# Controller.net
KiCad netlist of a schematic drawn in EAGLE
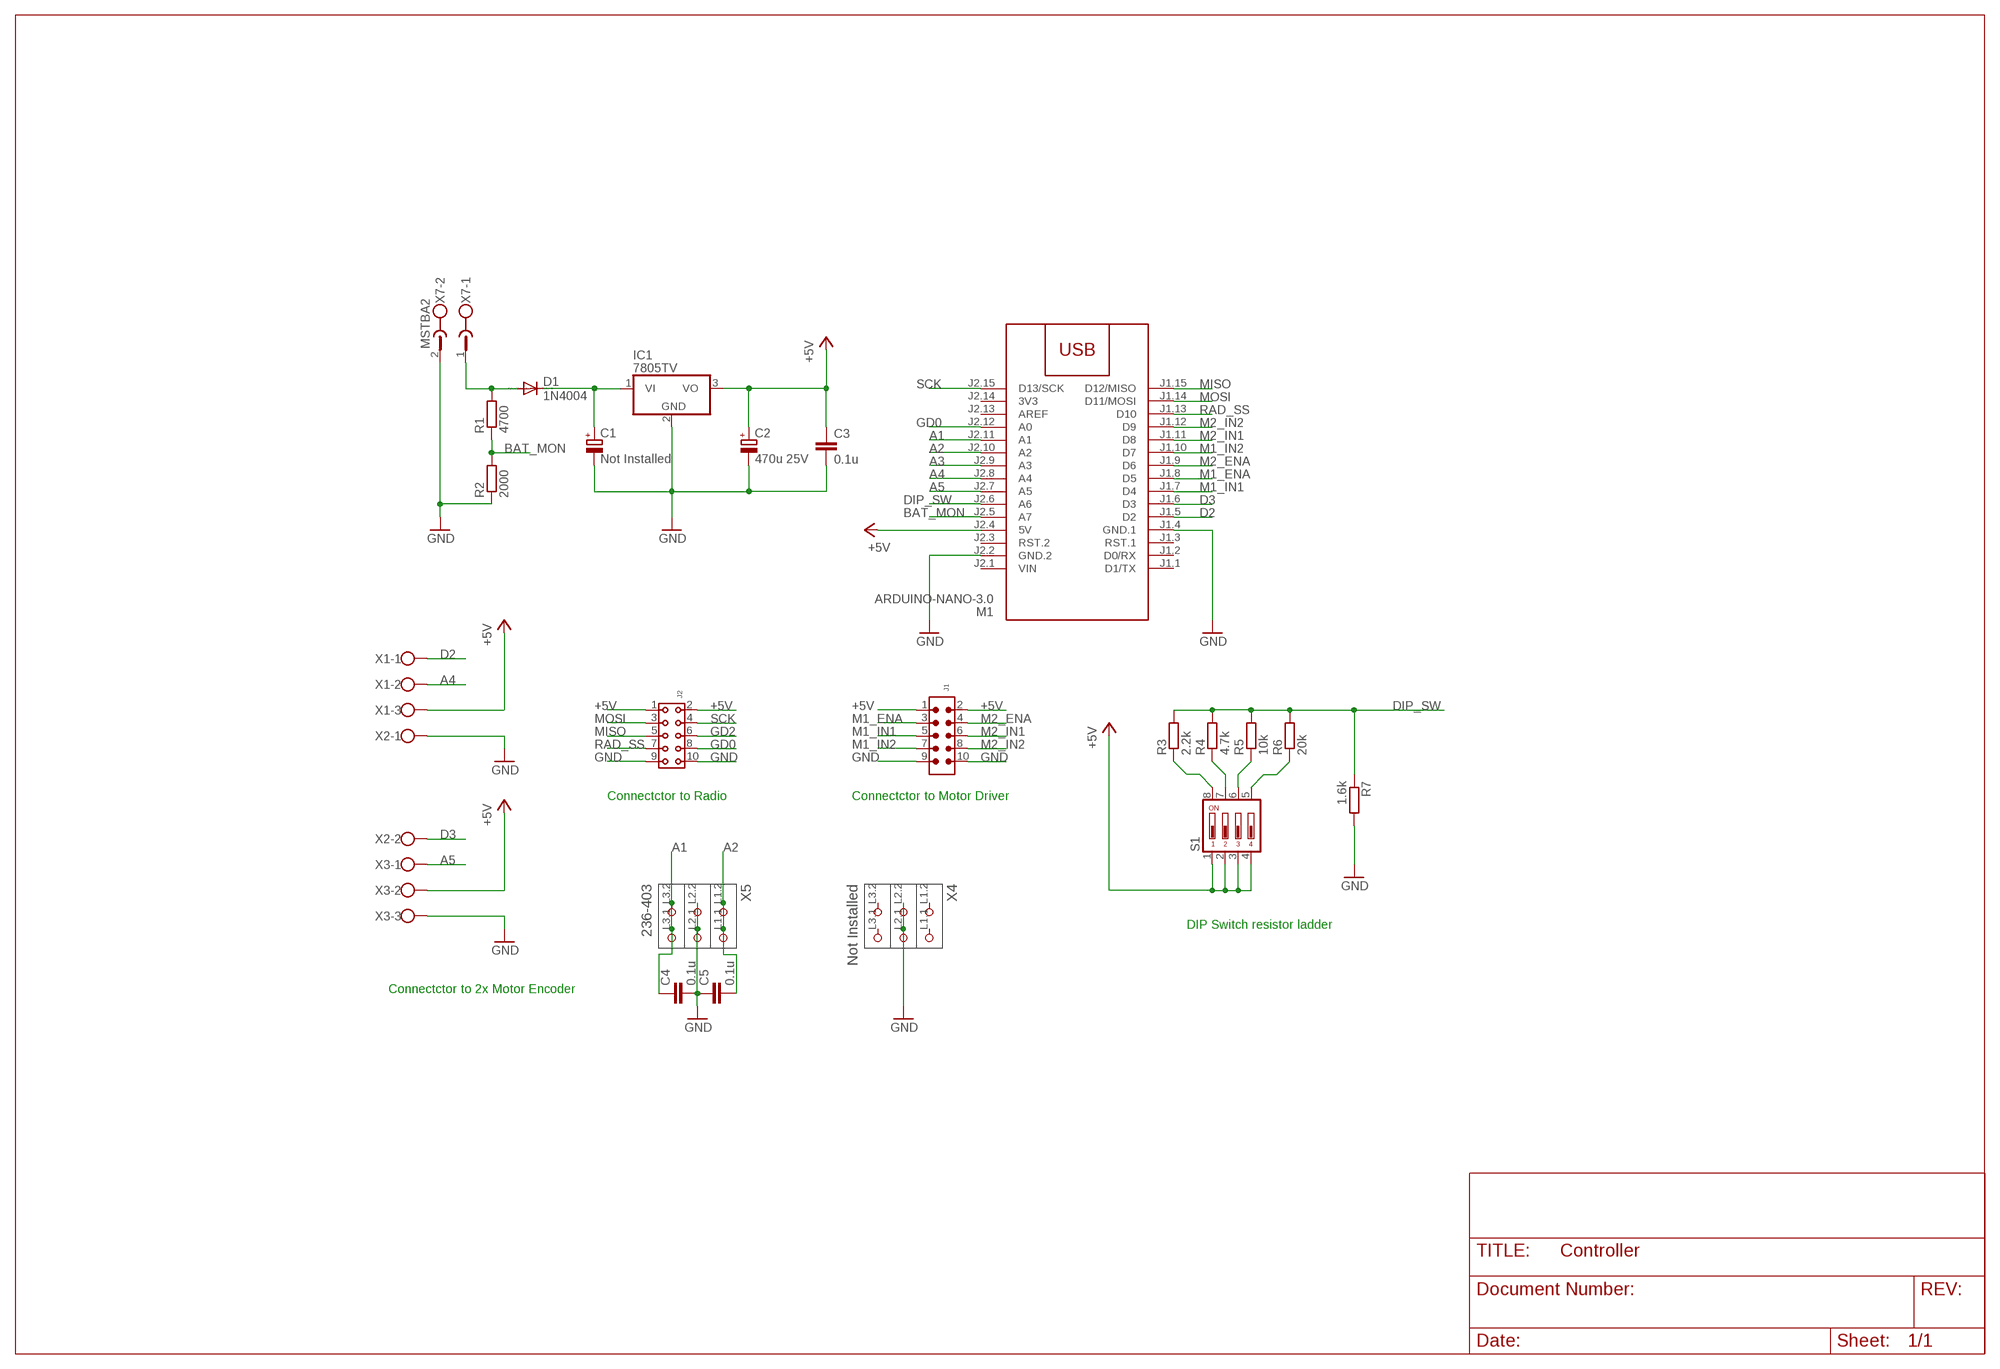
[diagram p0: schematic, sheet 1]

(export (version "E")
  (design (tool "Eeschema 10.0.6"))
  (components
    (comp (ref "C1")
      (value "Not Installed")
      (footprint "eagle-import:EB20D")
      (libsource (lib "eagle-import") (part "CPOL-EUE10-20"))
    )
    (comp (ref "C2")
      (value "470u 25V")
      (footprint "eagle-import:EB20D")
      (libsource (lib "eagle-import") (part "CPOL-EUE10-20"))
    )
    (comp (ref "C3")
      (value "0.1u")
      (footprint "eagle-import:C050-030X075")
      (libsource (lib "eagle-import") (part "C-EU050-030X075"))
    )
    (comp (ref "C4")
      (value "0.1u")
      (footprint "eagle-import:C050-030X075")
      (libsource (lib "eagle-import") (part "C-EU050-030X075"))
    )
    (comp (ref "C5")
      (value "0.1u")
      (footprint "eagle-import:C050-030X075")
      (libsource (lib "eagle-import") (part "C-EU050-030X075"))
    )
    (comp (ref "D1")
      (value "1N4004")
      (footprint "eagle-import:DO41-10")
      (libsource (lib "eagle-import") (part "1N4004"))
    )
    (comp (ref "IC1")
      (value "7805TV")
      (footprint "eagle-import:TO220V")
      (libsource (lib "eagle-import") (part "78TV05"))
    )
    (comp (ref "J1")
      (value "6120XX21621_61201021621")
      (footprint "eagle-import:61201021621")
      (libsource (lib "eagle-import") (part "6120XX21621_61201021621"))
    )
    (comp (ref "J2")
      (value "6130XX21821_61301021821")
      (footprint "eagle-import:61301021821")
      (libsource (lib "eagle-import") (part "6130XX21821_61301021821"))
    )
    (comp (ref "M1")
      (value "ARDUINO-NANO-3.0")
      (footprint "eagle-import:ARDUINO-NANO-3.0")
      (libsource (lib "eagle-import") (part "ARDUINO-NANO-3.0"))
    )
    (comp (ref "R1")
      (value "4700")
      (footprint "eagle-import:0207_12")
      (libsource (lib "eagle-import") (part "R-EU_0207/12"))
    )
    (comp (ref "R2")
      (value "2000")
      (footprint "eagle-import:0207_7")
      (libsource (lib "eagle-import") (part "R-EU_0207/7"))
    )
    (comp (ref "R3")
      (value "2.2k")
      (footprint "eagle-import:0207_5V")
      (libsource (lib "eagle-import") (part "R-EU_0207/5V"))
    )
    (comp (ref "R4")
      (value "4.7k")
      (footprint "eagle-import:0207_5V")
      (libsource (lib "eagle-import") (part "R-EU_0207/5V"))
    )
    (comp (ref "R5")
      (value "10k")
      (footprint "eagle-import:0207_5V")
      (libsource (lib "eagle-import") (part "R-EU_0207/5V"))
    )
    (comp (ref "R6")
      (value "20k")
      (footprint "eagle-import:0207_5V")
      (libsource (lib "eagle-import") (part "R-EU_0207/5V"))
    )
    (comp (ref "R7")
      (value "1.6k")
      (footprint "eagle-import:0207_5V")
      (libsource (lib "eagle-import") (part "R-EU_0207/5V"))
    )
    (comp (ref "S1")
      (value "DIP04YL")
      (footprint "eagle-import:DIP04YL")
      (libsource (lib "eagle-import") (part "DIP04YL"))
    )
    (comp (ref "X1")
      (value "W237-103")
      (footprint "eagle-import:W237-103")
      (fields (field (name "MPN") "237-103"))
      (libsource (lib "eagle-import") (part "W237-103"))
    )
    (comp (ref "X2")
      (value "W237-102")
      (footprint "eagle-import:W237-102")
      (fields (field (name "MPN") "237-102"))
      (libsource (lib "eagle-import") (part "W237-102"))
    )
    (comp (ref "X3")
      (value "W237-103")
      (footprint "eagle-import:W237-103")
      (fields (field (name "MPN") "237-103"))
      (libsource (lib "eagle-import") (part "W237-103"))
    )
    (comp (ref "X4")
      (value "Not Installed")
      (footprint "eagle-import:P-236-403")
      (libsource (lib "eagle-import") (part "236-403"))
    )
    (comp (ref "X5")
      (value "236-403")
      (footprint "eagle-import:P-236-403")
      (libsource (lib "eagle-import") (part "236-403"))
    )
    (comp (ref "X7")
      (value "MSTBA2")
      (footprint "eagle-import:MSTBA2")
      (fields (field (name "MF") "FARNELL") (field (name "MPN") "1757242"))
      (libsource (lib "eagle-import") (part "MSTBA2"))
    )
  )
  (nets
    (net (code "1") (name "+5V") (class "Default")
      (node (ref "C2") (pin "+") (pinfunction "+_+") (pintype "passive"))
      (node (ref "C3") (pin "1") (pinfunction "1_1") (pintype "passive"))
      (node (ref "IC1") (pin "3") (pinfunction "VO_3") (pintype "passive"))
      (node (ref "J1") (pin "1") (pinfunction "1_1") (pintype "passive"))
      (node (ref "J1") (pin "2") (pinfunction "2_2") (pintype "passive"))
      (node (ref "J2") (pin "1") (pinfunction "1_1") (pintype "passive"))
      (node (ref "J2") (pin "2") (pinfunction "2_2") (pintype "passive"))
      (node (ref "M1") (pin "J2.4") (pinfunction "5V_J2.4") (pintype "power_in"))
      (node (ref "S1") (pin "1") (pinfunction "1_1") (pintype "passive"))
      (node (ref "S1") (pin "2") (pinfunction "2_2") (pintype "passive"))
      (node (ref "S1") (pin "3") (pinfunction "3_3") (pintype "passive"))
      (node (ref "S1") (pin "4") (pinfunction "4_4") (pintype "passive"))
      (node (ref "X1") (pin "3") (pinfunction "KL_3") (pintype "passive"))
      (node (ref "X3") (pin "2") (pinfunction "KL_2") (pintype "passive"))
    )
    (net (code "2") (name "/3V3") (class "Default")
      (node (ref "M1") (pin "J2.14") (pinfunction "3V3_J2.14") (pintype "power_in"))
    )
    (net (code "3") (name "/A1") (class "Default")
      (node (ref "C4") (pin "1") (pinfunction "1_1") (pintype "passive"))
      (node (ref "M1") (pin "J2.11") (pinfunction "A1_J2.11") (pintype "bidirectional"))
      (node (ref "X5") (pin "L3.1") (pinfunction "P3.1_L3.1") (pintype "bidirectional"))
      (node (ref "X5") (pin "L3.2") (pinfunction "P3.2_L3.2") (pintype "bidirectional"))
    )
    (net (code "4") (name "/A2") (class "Default")
      (node (ref "C5") (pin "2") (pinfunction "2_2") (pintype "passive"))
      (node (ref "M1") (pin "J2.10") (pinfunction "A2_J2.10") (pintype "bidirectional"))
      (node (ref "X5") (pin "L1.1") (pinfunction "P1.1_L1.1") (pintype "bidirectional"))
      (node (ref "X5") (pin "L1.2") (pinfunction "P1.2_L1.2") (pintype "bidirectional"))
    )
    (net (code "5") (name "/A3") (class "Default")
      (node (ref "M1") (pin "J2.9") (pinfunction "A3_J2.9") (pintype "bidirectional"))
    )
    (net (code "6") (name "/A4") (class "Default")
      (node (ref "M1") (pin "J2.8") (pinfunction "A4_J2.8") (pintype "bidirectional"))
      (node (ref "X1") (pin "2") (pinfunction "KL_2") (pintype "passive"))
    )
    (net (code "7") (name "/A5") (class "Default")
      (node (ref "M1") (pin "J2.7") (pinfunction "A5_J2.7") (pintype "bidirectional"))
      (node (ref "X3") (pin "1") (pinfunction "KL_1") (pintype "passive"))
    )
    (net (code "8") (name "/BAT_MON") (class "Default")
      (node (ref "M1") (pin "J2.5") (pinfunction "A7_J2.5") (pintype "bidirectional"))
      (node (ref "R1") (pin "1") (pinfunction "1_1") (pintype "passive"))
      (node (ref "R2") (pin "2") (pinfunction "2_2") (pintype "passive"))
    )
    (net (code "9") (name "/D2") (class "Default")
      (node (ref "M1") (pin "J1.5") (pinfunction "D2_J1.5") (pintype "bidirectional"))
      (node (ref "X1") (pin "1") (pinfunction "KL_1") (pintype "passive"))
    )
    (net (code "10") (name "/D3") (class "Default")
      (node (ref "M1") (pin "J1.6") (pinfunction "D3_J1.6") (pintype "bidirectional"))
      (node (ref "X2") (pin "2") (pinfunction "KL_2") (pintype "passive"))
    )
    (net (code "11") (name "/DIP_SW") (class "Default")
      (node (ref "M1") (pin "J2.6") (pinfunction "A6_J2.6") (pintype "bidirectional"))
      (node (ref "R3") (pin "2") (pinfunction "2_2") (pintype "passive"))
      (node (ref "R4") (pin "2") (pinfunction "2_2") (pintype "passive"))
      (node (ref "R5") (pin "2") (pinfunction "2_2") (pintype "passive"))
      (node (ref "R6") (pin "2") (pinfunction "2_2") (pintype "passive"))
      (node (ref "R7") (pin "1") (pinfunction "1_1") (pintype "passive"))
    )
    (net (code "12") (name "/GD0") (class "Default")
      (node (ref "J2") (pin "8") (pinfunction "8_8") (pintype "passive"))
      (node (ref "M1") (pin "J2.12") (pinfunction "A0_J2.12") (pintype "bidirectional"))
    )
    (net (code "13") (name "/GD2") (class "Default")
      (node (ref "J2") (pin "6") (pinfunction "6_6") (pintype "passive"))
    )
    (net (code "14") (name "/M1_ENA") (class "Default")
      (node (ref "J1") (pin "3") (pinfunction "3_3") (pintype "passive"))
      (node (ref "M1") (pin "J1.8") (pinfunction "D5_J1.8") (pintype "bidirectional"))
    )
    (net (code "15") (name "/M1_IN1") (class "Default")
      (node (ref "J1") (pin "5") (pinfunction "5_5") (pintype "passive"))
      (node (ref "M1") (pin "J1.7") (pinfunction "D4_J1.7") (pintype "bidirectional"))
    )
    (net (code "16") (name "/M1_IN2") (class "Default")
      (node (ref "J1") (pin "7") (pinfunction "7_7") (pintype "passive"))
      (node (ref "M1") (pin "J1.10") (pinfunction "D7_J1.10") (pintype "bidirectional"))
    )
    (net (code "17") (name "/M2_ENA") (class "Default")
      (node (ref "J1") (pin "4") (pinfunction "4_4") (pintype "passive"))
      (node (ref "M1") (pin "J1.9") (pinfunction "D6_J1.9") (pintype "bidirectional"))
    )
    (net (code "18") (name "/M2_IN1") (class "Default")
      (node (ref "J1") (pin "6") (pinfunction "6_6") (pintype "passive"))
      (node (ref "M1") (pin "J1.11") (pinfunction "D8_J1.11") (pintype "bidirectional"))
    )
    (net (code "19") (name "/M2_IN2") (class "Default")
      (node (ref "J1") (pin "8") (pinfunction "8_8") (pintype "passive"))
      (node (ref "M1") (pin "J1.12") (pinfunction "D9_J1.12") (pintype "bidirectional"))
    )
    (net (code "20") (name "/MISO") (class "Default")
      (node (ref "J2") (pin "5") (pinfunction "5_5") (pintype "passive"))
      (node (ref "M1") (pin "J1.15") (pinfunction "D12/MISO_J1.15") (pintype "bidirectional"))
    )
    (net (code "21") (name "/MOSI") (class "Default")
      (node (ref "J2") (pin "3") (pinfunction "3_3") (pintype "passive"))
      (node (ref "M1") (pin "J1.14") (pinfunction "D11/MOSI_J1.14") (pintype "bidirectional"))
    )
    (net (code "22") (name "/RAD_SS") (class "Default")
      (node (ref "J2") (pin "7") (pinfunction "7_7") (pintype "passive"))
      (node (ref "M1") (pin "J1.13") (pinfunction "D10_J1.13") (pintype "bidirectional"))
    )
    (net (code "23") (name "/SCK") (class "Default")
      (node (ref "J2") (pin "4") (pinfunction "4_4") (pintype "passive"))
      (node (ref "M1") (pin "J2.15") (pinfunction "D13/SCK_J2.15") (pintype "bidirectional"))
    )
    (net (code "24") (name "/VIN") (class "Default")
      (node (ref "M1") (pin "J2.1") (pinfunction "VIN_J2.1") (pintype "power_in"))
    )
    (net (code "25") (name "GND") (class "Default")
      (node (ref "C1") (pin "-") (pinfunction "-_-") (pintype "passive"))
      (node (ref "C2") (pin "-") (pinfunction "-_-") (pintype "passive"))
      (node (ref "C3") (pin "2") (pinfunction "2_2") (pintype "passive"))
      (node (ref "C4") (pin "2") (pinfunction "2_2") (pintype "passive"))
      (node (ref "C5") (pin "1") (pinfunction "1_1") (pintype "passive"))
      (node (ref "IC1") (pin "2") (pinfunction "GND_2") (pintype "passive"))
      (node (ref "J1") (pin "10") (pinfunction "10_10") (pintype "passive"))
      (node (ref "J1") (pin "9") (pinfunction "9_9") (pintype "passive"))
      (node (ref "J2") (pin "10") (pinfunction "10_10") (pintype "passive"))
      (node (ref "J2") (pin "9") (pinfunction "9_9") (pintype "passive"))
      (node (ref "M1") (pin "J1.4") (pinfunction "GND.1_J1.4") (pintype "power_in"))
      (node (ref "M1") (pin "J2.2") (pinfunction "GND.2_J2.2") (pintype "power_in"))
      (node (ref "R2") (pin "1") (pinfunction "1_1") (pintype "passive"))
      (node (ref "R7") (pin "2") (pinfunction "2_2") (pintype "passive"))
      (node (ref "X2") (pin "1") (pinfunction "KL_1") (pintype "passive"))
      (node (ref "X3") (pin "3") (pinfunction "KL_3") (pintype "passive"))
      (node (ref "X4") (pin "L2.1") (pinfunction "P2.1_L2.1") (pintype "bidirectional"))
      (node (ref "X4") (pin "L2.2") (pinfunction "P2.2_L2.2") (pintype "bidirectional"))
      (node (ref "X5") (pin "L2.1") (pinfunction "P2.1_L2.1") (pintype "bidirectional"))
      (node (ref "X5") (pin "L2.2") (pinfunction "P2.2_L2.2") (pintype "bidirectional"))
      (node (ref "X7") (pin "2") (pinfunction "1_2") (pintype "passive"))
    )
    (net (code "26") (name "Net-(D1-PadA)") (class "Default")
      (node (ref "D1") (pin "A") (pinfunction "A_A") (pintype "passive"))
      (node (ref "R1") (pin "2") (pinfunction "2_2") (pintype "passive"))
      (node (ref "X7") (pin "1") (pinfunction "1_1") (pintype "passive"))
    )
    (net (code "27") (name "Net-(IC1-VI)") (class "Default")
      (node (ref "C1") (pin "+") (pinfunction "+_+") (pintype "passive"))
      (node (ref "D1") (pin "C") (pinfunction "C_C") (pintype "passive"))
      (node (ref "IC1") (pin "1") (pinfunction "VI_1") (pintype "input"))
    )
    (net (code "28") (name "Net-(R3-Pad1)") (class "Default")
      (node (ref "R3") (pin "1") (pinfunction "1_1") (pintype "passive"))
      (node (ref "S1") (pin "8") (pinfunction "8_8") (pintype "passive"))
    )
    (net (code "29") (name "Net-(R4-Pad1)") (class "Default")
      (node (ref "R4") (pin "1") (pinfunction "1_1") (pintype "passive"))
      (node (ref "S1") (pin "7") (pinfunction "7_7") (pintype "passive"))
    )
    (net (code "30") (name "Net-(R5-Pad1)") (class "Default")
      (node (ref "R5") (pin "1") (pinfunction "1_1") (pintype "passive"))
      (node (ref "S1") (pin "6") (pinfunction "6_6") (pintype "passive"))
    )
    (net (code "31") (name "Net-(R6-Pad1)") (class "Default")
      (node (ref "R6") (pin "1") (pinfunction "1_1") (pintype "passive"))
      (node (ref "S1") (pin "5") (pinfunction "5_5") (pintype "passive"))
    )
    (net (code "32") (name "unconnected-(M1-AREF-PadJ2.13)") (class "Default")
      (node (ref "M1") (pin "J2.13") (pinfunction "AREF_J2.13") (pintype "bidirectional"))
    )
    (net (code "33") (name "unconnected-(M1-D0{slash}RX-PadJ1.2)") (class "Default")
      (node (ref "M1") (pin "J1.2") (pinfunction "D0/RX_J1.2") (pintype "bidirectional"))
    )
    (net (code "34") (name "unconnected-(M1-D1{slash}TX-PadJ1.1)") (class "Default")
      (node (ref "M1") (pin "J1.1") (pinfunction "D1/TX_J1.1") (pintype "bidirectional"))
    )
    (net (code "35") (name "unconnected-(M1-RST.1-PadJ1.3)") (class "Default")
      (node (ref "M1") (pin "J1.3") (pinfunction "RST.1_J1.3") (pintype "bidirectional"))
    )
    (net (code "36") (name "unconnected-(M1-RST.2-PadJ2.3)") (class "Default")
      (node (ref "M1") (pin "J2.3") (pinfunction "RST.2_J2.3") (pintype "bidirectional"))
    )
    (net (code "37") (name "unconnected-(X4-P1.1-PadL1.1)") (class "Default")
      (node (ref "X4") (pin "L1.1") (pinfunction "P1.1_L1.1") (pintype "bidirectional"))
    )
    (net (code "38") (name "unconnected-(X4-P1.2-PadL1.2)") (class "Default")
      (node (ref "X4") (pin "L1.2") (pinfunction "P1.2_L1.2") (pintype "bidirectional"))
    )
    (net (code "39") (name "unconnected-(X4-P3.1-PadL3.1)") (class "Default")
      (node (ref "X4") (pin "L3.1") (pinfunction "P3.1_L3.1") (pintype "bidirectional"))
    )
    (net (code "40") (name "unconnected-(X4-P3.2-PadL3.2)") (class "Default")
      (node (ref "X4") (pin "L3.2") (pinfunction "P3.2_L3.2") (pintype "bidirectional"))
    )
  )
)
